# 555Timer.net
KiCad netlist of a schematic drawn in Altium Designer
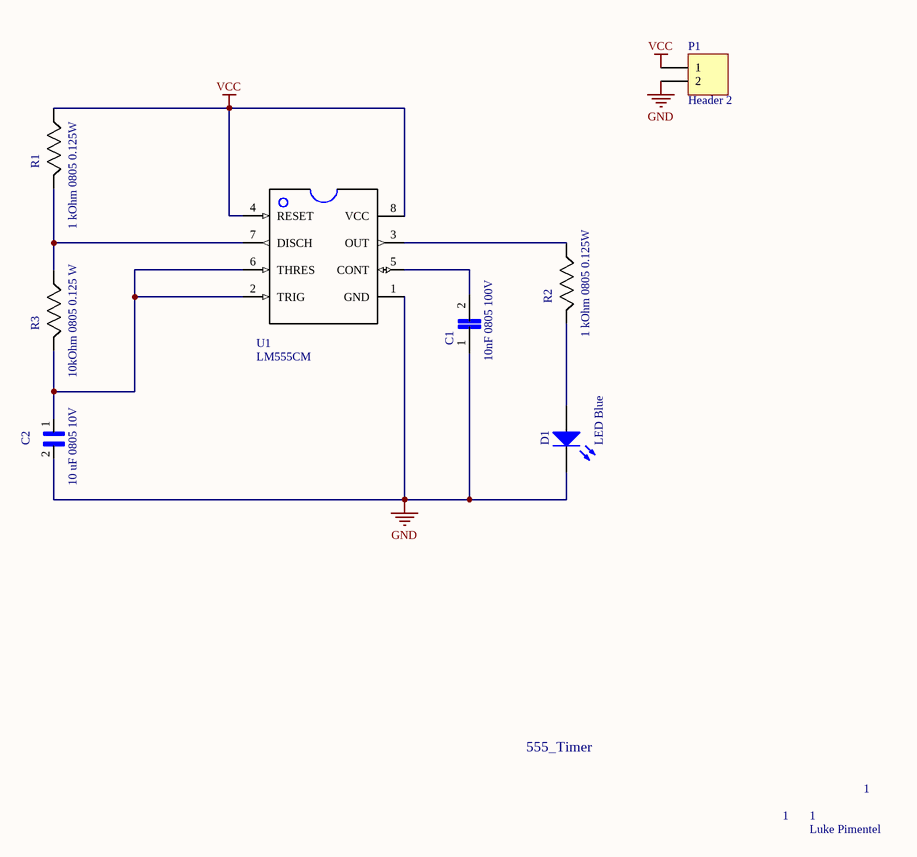
[diagram p0: 555Timer.SchDoc]

(export (version "E")
  (design (tool "Eeschema 10.0.6"))
  (components
    (comp (ref "C1")
      (value "10nF 0805 100V")
      (footprint "C0805")
      (description "0805 10 nF 100 V ±10% Tolerance X7R SMT Multilayer Ceramic Capacitor")
      (fields (field (name "MF") "Murata") (field (name "MP") "GRM21BR72A103KA01L"))
      (libsource (lib "555_Timer") (part "GRM21BR72A103KA01L"))
    )
    (comp (ref "C2")
      (value "10 uF 0805 10V")
      (footprint "C0805")
      (description "0805 10 uF 10 V ±10 % Tolerance X7R Surface Mount Multilayer Ceramic Capacitor")
      (fields (field (name "MF") "Murata") (field (name "MP") "GCM21BR71A106KE22L"))
      (libsource (lib "555_Timer") (part "GCM21BR71A106KE22L"))
    )
    (comp (ref "D1")
      (value "LED Blue")
      (footprint "LED1206")
      (description "SM1206 Series Blue 30° Water Clear 408 nm 3.4 V 1206 Surface Mount LED")
      (libsource (lib "555_Timer") (part "SM1206UV-405-IL"))
    )
    (comp (ref "P1")
      (value "Header 2")
      (footprint "HDR1X2")
      (description "Header, 2-Pin")
      (fields (field (name "PUBLISHER") "Altium Limited"))
      (libsource (lib "555_Timer") (part "Header 2"))
    )
    (comp (ref "R1")
      (value "1 kOhm 0805 0.125W")
      (footprint "R0805")
      (description "RC Series 0805 0.125 W 1 kOhms 1%  ±100 ppm/°C SMT Thick Film Chip Resistor")
      (fields (field (name "MF") "Yageo") (field (name "MP") "RC0805FR-0710KL"))
      (libsource (lib "555_Timer") (part "RC0805JR-071KL"))
    )
    (comp (ref "R2")
      (value "1 kOhm 0805 0.125W")
      (footprint "R0805")
      (description "RC Series 0805 0.125 W 1 kOhms 1%  ±100 ppm/°C SMT Thick Film Chip Resistor")
      (fields (field (name "MF") "Yageo") (field (name "MP") "RC0805FR-0710KL"))
      (libsource (lib "555_Timer") (part "RC0805JR-071KL"))
    )
    (comp (ref "R3")
      (value "10kOhm 0805 0.125 W")
      (footprint "R0805")
      (description "RC Series 0805 0.125 W 10 kOhms 1% ±100 ppm/°C SMT Thick Film Chip Resistor")
      (fields (field (name "MF") "Yageo") (field (name "MP") "RC0805FR-0710KL"))
      (libsource (lib "555_Timer") (part "RC0805FR-0710KL"))
    )
    (comp (ref "U1")
      (value "LM555CM")
      (footprint "SO08")
      (description "555 SOIC")
      (fields (field (name "MF") "Texas Instruments"))
      (libsource (lib "555_Timer") (part "LM555CM"))
    )
  )
  (nets
    (net (code "1") (name "GND") (class "Default")
      (node (ref "C1") (pin "1") (pinfunction "1_1") (pintype "passive"))
      (node (ref "C2") (pin "2") (pinfunction "2_2") (pintype "passive"))
      (node (ref "D1") (pin "2") (pinfunction "C_2") (pintype "passive"))
      (node (ref "P1") (pin "2") (pinfunction "2_2") (pintype "passive"))
      (node (ref "U1") (pin "1") (pinfunction "GND_1") (pintype "passive"))
    )
    (net (code "2") (name "Net-(D1-A)") (class "Default")
      (node (ref "D1") (pin "1") (pinfunction "A_1") (pintype "passive"))
      (node (ref "R2") (pin "1") (pinfunction "1_1") (pintype "passive"))
    )
    (net (code "3") (name "Net-(U1-CONT)") (class "Default")
      (node (ref "C1") (pin "2") (pinfunction "2_2") (pintype "passive"))
      (node (ref "U1") (pin "5") (pinfunction "CONT_5") (pintype "bidirectional"))
    )
    (net (code "4") (name "Net-(U1-DISCH)") (class "Default")
      (node (ref "R1") (pin "1") (pinfunction "1_1") (pintype "passive"))
      (node (ref "R3") (pin "2") (pinfunction "2_2") (pintype "passive"))
      (node (ref "U1") (pin "7") (pinfunction "DISCH_7") (pintype "output"))
    )
    (net (code "5") (name "Net-(U1-OUT)") (class "Default")
      (node (ref "R2") (pin "2") (pinfunction "2_2") (pintype "passive"))
      (node (ref "U1") (pin "3") (pinfunction "OUT_3") (pintype "output"))
    )
    (net (code "6") (name "Net-(U1-THRES)") (class "Default")
      (node (ref "C2") (pin "1") (pinfunction "1_1") (pintype "passive"))
      (node (ref "R3") (pin "1") (pinfunction "1_1") (pintype "passive"))
      (node (ref "U1") (pin "2") (pinfunction "TRIG_2") (pintype "input"))
      (node (ref "U1") (pin "6") (pinfunction "THRES_6") (pintype "input"))
    )
    (net (code "7") (name "VCC") (class "Default")
      (node (ref "P1") (pin "1") (pinfunction "1_1") (pintype "passive"))
      (node (ref "R1") (pin "2") (pinfunction "2_2") (pintype "passive"))
      (node (ref "U1") (pin "4") (pinfunction "RESET_4") (pintype "input"))
      (node (ref "U1") (pin "8") (pinfunction "VCC_8") (pintype "power_in"))
    )
  )
)
